# CAN_Shield.net
KiCad netlist of a schematic drawn in EAGLE
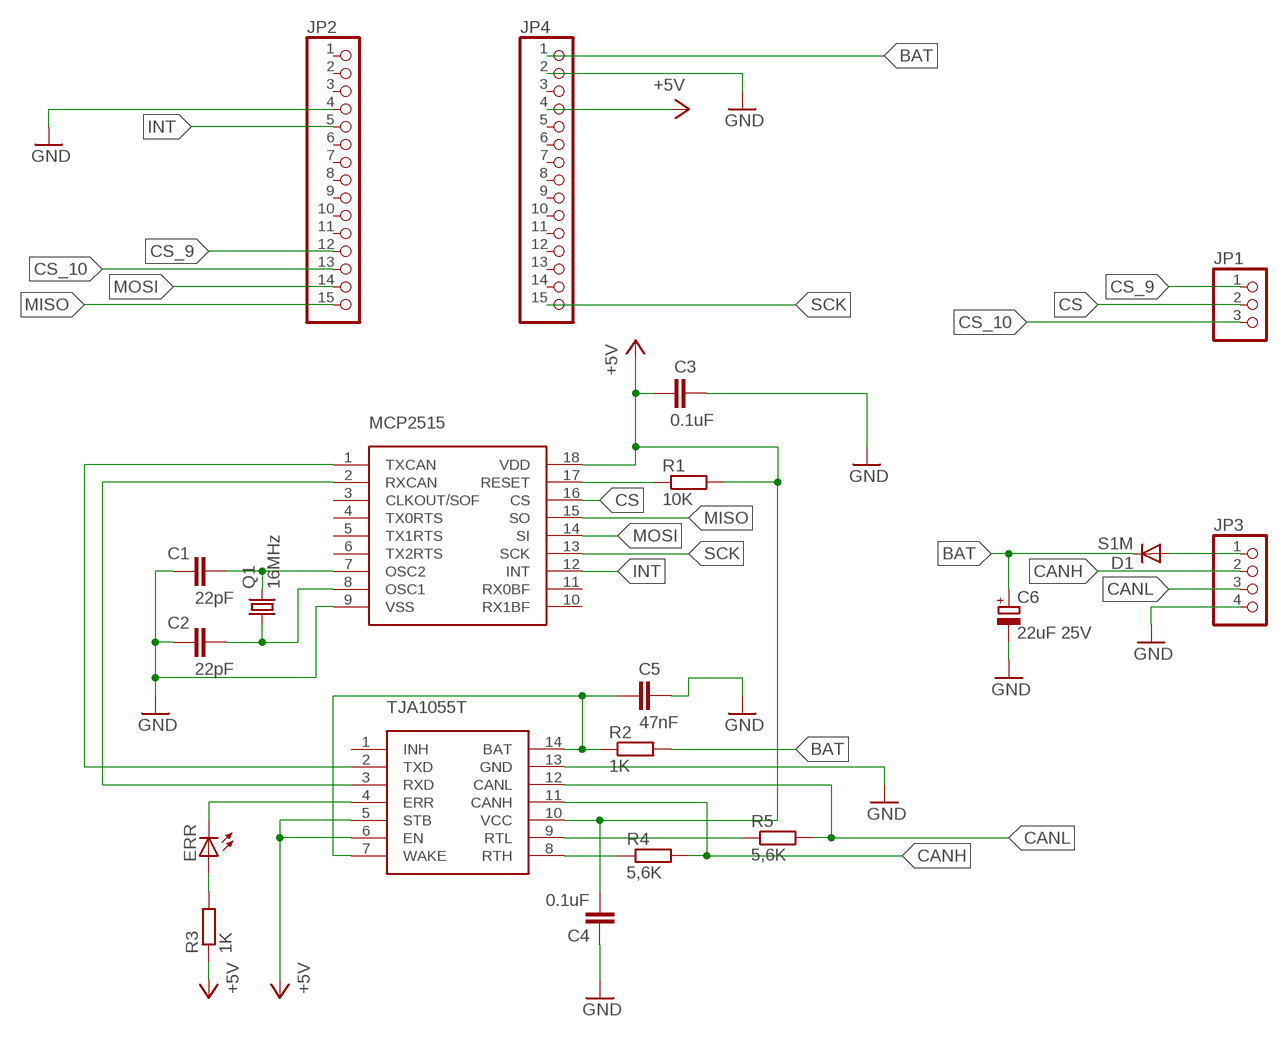
[diagram p0: schematic, sheet 1]

(export (version "E")
  (design (tool "Eeschema 10.0.6"))
  (components
    (comp (ref "C1")
      (value "22pF")
      (footprint "eagle-import:C0805")
      (libsource (lib "eagle-import") (part "C-EUC0805"))
    )
    (comp (ref "C2")
      (value "22pF")
      (footprint "eagle-import:C0805")
      (libsource (lib "eagle-import") (part "C-EUC0805"))
    )
    (comp (ref "C3")
      (value "0.1uF")
      (footprint "eagle-import:C0805")
      (libsource (lib "eagle-import") (part "C-EUC0805"))
    )
    (comp (ref "C4")
      (value "0.1uF")
      (footprint "eagle-import:C0805")
      (libsource (lib "eagle-import") (part "C-EUC0805"))
    )
    (comp (ref "C5")
      (value "47nF")
      (footprint "eagle-import:C0805")
      (libsource (lib "eagle-import") (part "C-EUC0805"))
    )
    (comp (ref "C6")
      (value "22uF 25V")
      (footprint "eagle-import:SMC_C")
      (libsource (lib "eagle-import") (part "CPOL-EUSMCC"))
    )
    (comp (ref "D1")
      (value "S1M")
      (footprint "eagle-import:SMA")
      (libsource (lib "eagle-import") (part "S1M"))
    )
    (comp (ref "ERR")
      (value "LEDCHIP-LED0805")
      (footprint "eagle-import:CHIP-LED0805")
      (libsource (lib "eagle-import") (part "LEDCHIP-LED0805"))
    )
    (comp (ref "JP1")
      (value "PINHD-1X3")
      (footprint "eagle-import:1X03")
      (libsource (lib "eagle-import") (part "PINHD-1X3"))
    )
    (comp (ref "JP2")
      (value "PINHD-1X15")
      (footprint "eagle-import:1X15")
      (libsource (lib "eagle-import") (part "PINHD-1X15"))
    )
    (comp (ref "JP3")
      (value "PINHD-1X4-1")
      (footprint "eagle-import:1X04")
      (libsource (lib "eagle-import") (part "PINHD-1X4-1"))
    )
    (comp (ref "JP4")
      (value "PINHD-1X15")
      (footprint "eagle-import:1X15")
      (libsource (lib "eagle-import") (part "PINHD-1X15"))
    )
    (comp (ref "MCP2515")
      (value "MCP2515")
      (footprint "eagle-import:SO18-1")
      (libsource (lib "eagle-import") (part "MCP2515"))
    )
    (comp (ref "Q1")
      (value "16MHz")
      (footprint "eagle-import:HC49_S")
      (libsource (lib "eagle-import") (part "CRYSTALHC49S"))
    )
    (comp (ref "R1")
      (value "10K")
      (footprint "eagle-import:R0805")
      (libsource (lib "eagle-import") (part "R-EU_R0805"))
    )
    (comp (ref "R2")
      (value "1K")
      (footprint "eagle-import:R0805")
      (libsource (lib "eagle-import") (part "R-EU_R0805"))
    )
    (comp (ref "R3")
      (value "1K")
      (footprint "eagle-import:R0805")
      (libsource (lib "eagle-import") (part "R-EU_R0805"))
    )
    (comp (ref "R4")
      (value "5,6K")
      (footprint "eagle-import:R0805")
      (libsource (lib "eagle-import") (part "R-EU_R0805"))
    )
    (comp (ref "R5")
      (value "5,6K")
      (footprint "eagle-import:R0805")
      (libsource (lib "eagle-import") (part "R-EU_R0805"))
    )
    (comp (ref "TJA1055T")
      (value "TJA1055T")
      (footprint "eagle-import:SO-14W")
      (libsource (lib "eagle-import") (part "TJA1055T"))
    )
  )
  (nets
    (net (code "1") (name "+5V") (class "Default")
      (node (ref "C3") (pin "1") (pinfunction "1_1") (pintype "passive"))
      (node (ref "C4") (pin "2") (pinfunction "2_2") (pintype "passive"))
      (node (ref "JP4") (pin "4") (pinfunction "4_4") (pintype "passive"))
      (node (ref "MCP2515") (pin "18") (pinfunction "VDD_18") (pintype "power_in"))
      (node (ref "R1") (pin "2") (pinfunction "2_2") (pintype "passive"))
      (node (ref "R3") (pin "1") (pinfunction "1_1") (pintype "passive"))
      (node (ref "TJA1055T") (pin "10") (pinfunction "VCC_10") (pintype "power_in"))
      (node (ref "TJA1055T") (pin "5") (pinfunction "STB_5") (pintype "input"))
      (node (ref "TJA1055T") (pin "6") (pinfunction "EN_6") (pintype "input"))
    )
    (net (code "2") (name "BAT") (class "Default")
      (node (ref "C6") (pin "+") (pinfunction "+_+") (pintype "passive"))
      (node (ref "D1") (pin "C") (pinfunction "C_C") (pintype "passive"))
      (node (ref "JP4") (pin "1") (pinfunction "1_1") (pintype "passive"))
      (node (ref "R2") (pin "2") (pinfunction "2_2") (pintype "passive"))
    )
    (net (code "3") (name "CANH") (class "Default")
      (node (ref "JP3") (pin "2") (pinfunction "2_2") (pintype "passive"))
      (node (ref "R4") (pin "2") (pinfunction "2_2") (pintype "passive"))
      (node (ref "TJA1055T") (pin "11") (pinfunction "CANH_11") (pintype "bidirectional"))
    )
    (net (code "4") (name "CANL") (class "Default")
      (node (ref "JP3") (pin "3") (pinfunction "3_3") (pintype "passive"))
      (node (ref "R5") (pin "2") (pinfunction "2_2") (pintype "passive"))
      (node (ref "TJA1055T") (pin "12") (pinfunction "CANL_12") (pintype "bidirectional"))
    )
    (net (code "5") (name "CS") (class "Default")
      (node (ref "JP1") (pin "2") (pinfunction "2_2") (pintype "passive"))
      (node (ref "MCP2515") (pin "16") (pinfunction "CS_16") (pintype "bidirectional"))
    )
    (net (code "6") (name "CS_9") (class "Default")
      (node (ref "JP1") (pin "1") (pinfunction "1_1") (pintype "passive"))
      (node (ref "JP2") (pin "12") (pinfunction "12_12") (pintype "passive"))
    )
    (net (code "7") (name "CS_10") (class "Default")
      (node (ref "JP1") (pin "3") (pinfunction "3_3") (pintype "passive"))
      (node (ref "JP2") (pin "13") (pinfunction "13_13") (pintype "passive"))
    )
    (net (code "8") (name "GND") (class "Default")
      (node (ref "C1") (pin "1") (pinfunction "1_1") (pintype "passive"))
      (node (ref "C2") (pin "1") (pinfunction "1_1") (pintype "passive"))
      (node (ref "C3") (pin "2") (pinfunction "2_2") (pintype "passive"))
      (node (ref "C4") (pin "1") (pinfunction "1_1") (pintype "passive"))
      (node (ref "C5") (pin "2") (pinfunction "2_2") (pintype "passive"))
      (node (ref "C6") (pin "-") (pinfunction "-_-") (pintype "passive"))
      (node (ref "JP2") (pin "4") (pinfunction "4_4") (pintype "passive"))
      (node (ref "JP3") (pin "4") (pinfunction "4_4") (pintype "passive"))
      (node (ref "JP4") (pin "2") (pinfunction "2_2") (pintype "passive"))
      (node (ref "MCP2515") (pin "9") (pinfunction "VSS_9") (pintype "power_in"))
      (node (ref "TJA1055T") (pin "13") (pinfunction "GND_13") (pintype "power_in"))
    )
    (net (code "9") (name "INT") (class "Default")
      (node (ref "JP2") (pin "5") (pinfunction "5_5") (pintype "passive"))
      (node (ref "MCP2515") (pin "12") (pinfunction "INT_12") (pintype "bidirectional"))
    )
    (net (code "10") (name "MISO") (class "Default")
      (node (ref "JP2") (pin "15") (pinfunction "15_15") (pintype "passive"))
      (node (ref "MCP2515") (pin "15") (pinfunction "SO_15") (pintype "bidirectional"))
    )
    (net (code "11") (name "MOSI") (class "Default")
      (node (ref "JP2") (pin "14") (pinfunction "14_14") (pintype "passive"))
      (node (ref "MCP2515") (pin "14") (pinfunction "SI_14") (pintype "bidirectional"))
    )
    (net (code "12") (name "Net-(D1-PadA)") (class "Default")
      (node (ref "D1") (pin "A") (pinfunction "A_A") (pintype "passive"))
      (node (ref "JP3") (pin "1") (pinfunction "1_1") (pintype "passive"))
    )
    (net (code "13") (name "Net-(ERR-PadA)") (class "Default")
      (node (ref "ERR") (pin "A") (pinfunction "A_A") (pintype "passive"))
      (node (ref "R3") (pin "2") (pinfunction "2_2") (pintype "passive"))
    )
    (net (code "14") (name "Net-(MCP2515-OSC1)") (class "Default")
      (node (ref "C2") (pin "2") (pinfunction "2_2") (pintype "passive"))
      (node (ref "MCP2515") (pin "8") (pinfunction "OSC1_8") (pintype "bidirectional"))
      (node (ref "Q1") (pin "1") (pinfunction "1_1") (pintype "passive"))
    )
    (net (code "15") (name "Net-(MCP2515-OSC2)") (class "Default")
      (node (ref "C1") (pin "2") (pinfunction "2_2") (pintype "passive"))
      (node (ref "MCP2515") (pin "7") (pinfunction "OSC2_7") (pintype "bidirectional"))
      (node (ref "Q1") (pin "2") (pinfunction "2_2") (pintype "passive"))
    )
    (net (code "16") (name "Net-(MCP2515-RESET)") (class "Default")
      (node (ref "MCP2515") (pin "17") (pinfunction "RESET_17") (pintype "bidirectional"))
      (node (ref "R1") (pin "1") (pinfunction "1_1") (pintype "passive"))
    )
    (net (code "17") (name "Net-(MCP2515-RXCAN)") (class "Default")
      (node (ref "MCP2515") (pin "2") (pinfunction "RXCAN_2") (pintype "bidirectional"))
      (node (ref "TJA1055T") (pin "3") (pinfunction "RXD_3") (pintype "bidirectional"))
    )
    (net (code "18") (name "Net-(MCP2515-TXCAN)") (class "Default")
      (node (ref "MCP2515") (pin "1") (pinfunction "TXCAN_1") (pintype "bidirectional"))
      (node (ref "TJA1055T") (pin "2") (pinfunction "TXD_2") (pintype "bidirectional"))
    )
    (net (code "19") (name "Net-(TJA1055T-BAT)") (class "Default")
      (node (ref "C5") (pin "1") (pinfunction "1_1") (pintype "passive"))
      (node (ref "R2") (pin "1") (pinfunction "1_1") (pintype "passive"))
      (node (ref "TJA1055T") (pin "14") (pinfunction "BAT_14") (pintype "input"))
      (node (ref "TJA1055T") (pin "7") (pinfunction "WAKE_7") (pintype "input"))
    )
    (net (code "20") (name "Net-(TJA1055T-ERR)") (class "Default")
      (node (ref "ERR") (pin "C") (pinfunction "C_C") (pintype "passive"))
      (node (ref "TJA1055T") (pin "4") (pinfunction "ERR_4") (pintype "output"))
    )
    (net (code "21") (name "Net-(TJA1055T-RTH)") (class "Default")
      (node (ref "R4") (pin "1") (pinfunction "1_1") (pintype "passive"))
      (node (ref "TJA1055T") (pin "8") (pinfunction "RTH_8") (pintype "bidirectional"))
    )
    (net (code "22") (name "Net-(TJA1055T-RTL)") (class "Default")
      (node (ref "R5") (pin "1") (pinfunction "1_1") (pintype "passive"))
      (node (ref "TJA1055T") (pin "9") (pinfunction "RTL_9") (pintype "bidirectional"))
    )
    (net (code "23") (name "SCK") (class "Default")
      (node (ref "JP4") (pin "15") (pinfunction "15_15") (pintype "passive"))
      (node (ref "MCP2515") (pin "13") (pinfunction "SCK_13") (pintype "bidirectional"))
    )
    (net (code "24") (name "unconnected-(JP2-Pad1)") (class "Default")
      (node (ref "JP2") (pin "1") (pinfunction "1_1") (pintype "passive"))
    )
    (net (code "25") (name "unconnected-(JP2-Pad2)") (class "Default")
      (node (ref "JP2") (pin "2") (pinfunction "2_2") (pintype "passive"))
    )
    (net (code "26") (name "unconnected-(JP2-Pad3)") (class "Default")
      (node (ref "JP2") (pin "3") (pinfunction "3_3") (pintype "passive"))
    )
    (net (code "27") (name "unconnected-(JP2-Pad6)") (class "Default")
      (node (ref "JP2") (pin "6") (pinfunction "6_6") (pintype "passive"))
    )
    (net (code "28") (name "unconnected-(JP2-Pad7)") (class "Default")
      (node (ref "JP2") (pin "7") (pinfunction "7_7") (pintype "passive"))
    )
    (net (code "29") (name "unconnected-(JP2-Pad8)") (class "Default")
      (node (ref "JP2") (pin "8") (pinfunction "8_8") (pintype "passive"))
    )
    (net (code "30") (name "unconnected-(JP2-Pad9)") (class "Default")
      (node (ref "JP2") (pin "9") (pinfunction "9_9") (pintype "passive"))
    )
    (net (code "31") (name "unconnected-(JP2-Pad10)") (class "Default")
      (node (ref "JP2") (pin "10") (pinfunction "10_10") (pintype "passive"))
    )
    (net (code "32") (name "unconnected-(JP2-Pad11)") (class "Default")
      (node (ref "JP2") (pin "11") (pinfunction "11_11") (pintype "passive"))
    )
    (net (code "33") (name "unconnected-(JP4-Pad3)") (class "Default")
      (node (ref "JP4") (pin "3") (pinfunction "3_3") (pintype "passive"))
    )
    (net (code "34") (name "unconnected-(JP4-Pad5)") (class "Default")
      (node (ref "JP4") (pin "5") (pinfunction "5_5") (pintype "passive"))
    )
    (net (code "35") (name "unconnected-(JP4-Pad6)") (class "Default")
      (node (ref "JP4") (pin "6") (pinfunction "6_6") (pintype "passive"))
    )
    (net (code "36") (name "unconnected-(JP4-Pad7)") (class "Default")
      (node (ref "JP4") (pin "7") (pinfunction "7_7") (pintype "passive"))
    )
    (net (code "37") (name "unconnected-(JP4-Pad8)") (class "Default")
      (node (ref "JP4") (pin "8") (pinfunction "8_8") (pintype "passive"))
    )
    (net (code "38") (name "unconnected-(JP4-Pad9)") (class "Default")
      (node (ref "JP4") (pin "9") (pinfunction "9_9") (pintype "passive"))
    )
    (net (code "39") (name "unconnected-(JP4-Pad10)") (class "Default")
      (node (ref "JP4") (pin "10") (pinfunction "10_10") (pintype "passive"))
    )
    (net (code "40") (name "unconnected-(JP4-Pad11)") (class "Default")
      (node (ref "JP4") (pin "11") (pinfunction "11_11") (pintype "passive"))
    )
    (net (code "41") (name "unconnected-(JP4-Pad12)") (class "Default")
      (node (ref "JP4") (pin "12") (pinfunction "12_12") (pintype "passive"))
    )
    (net (code "42") (name "unconnected-(JP4-Pad13)") (class "Default")
      (node (ref "JP4") (pin "13") (pinfunction "13_13") (pintype "passive"))
    )
    (net (code "43") (name "unconnected-(JP4-Pad14)") (class "Default")
      (node (ref "JP4") (pin "14") (pinfunction "14_14") (pintype "passive"))
    )
    (net (code "44") (name "unconnected-(MCP2515-CLKOUT{slash}SOF-Pad3)") (class "Default")
      (node (ref "MCP2515") (pin "3") (pinfunction "CLKOUT/SOF_3") (pintype "bidirectional"))
    )
    (net (code "45") (name "unconnected-(MCP2515-RX0BF-Pad11)") (class "Default")
      (node (ref "MCP2515") (pin "11") (pinfunction "RX0BF_11") (pintype "bidirectional"))
    )
    (net (code "46") (name "unconnected-(MCP2515-RX1BF-Pad10)") (class "Default")
      (node (ref "MCP2515") (pin "10") (pinfunction "RX1BF_10") (pintype "bidirectional"))
    )
    (net (code "47") (name "unconnected-(MCP2515-TX0RTS-Pad4)") (class "Default")
      (node (ref "MCP2515") (pin "4") (pinfunction "TX0RTS_4") (pintype "bidirectional"))
    )
    (net (code "48") (name "unconnected-(MCP2515-TX1RTS-Pad5)") (class "Default")
      (node (ref "MCP2515") (pin "5") (pinfunction "TX1RTS_5") (pintype "bidirectional"))
    )
    (net (code "49") (name "unconnected-(MCP2515-TX2RTS-Pad6)") (class "Default")
      (node (ref "MCP2515") (pin "6") (pinfunction "TX2RTS_6") (pintype "bidirectional"))
    )
    (net (code "50") (name "unconnected-(TJA1055T-INH-Pad1)") (class "Default")
      (node (ref "TJA1055T") (pin "1") (pinfunction "INH_1") (pintype "output"))
    )
  )
)
